# led_driver.net
KiCad netlist of a schematic drawn in Altium Designer
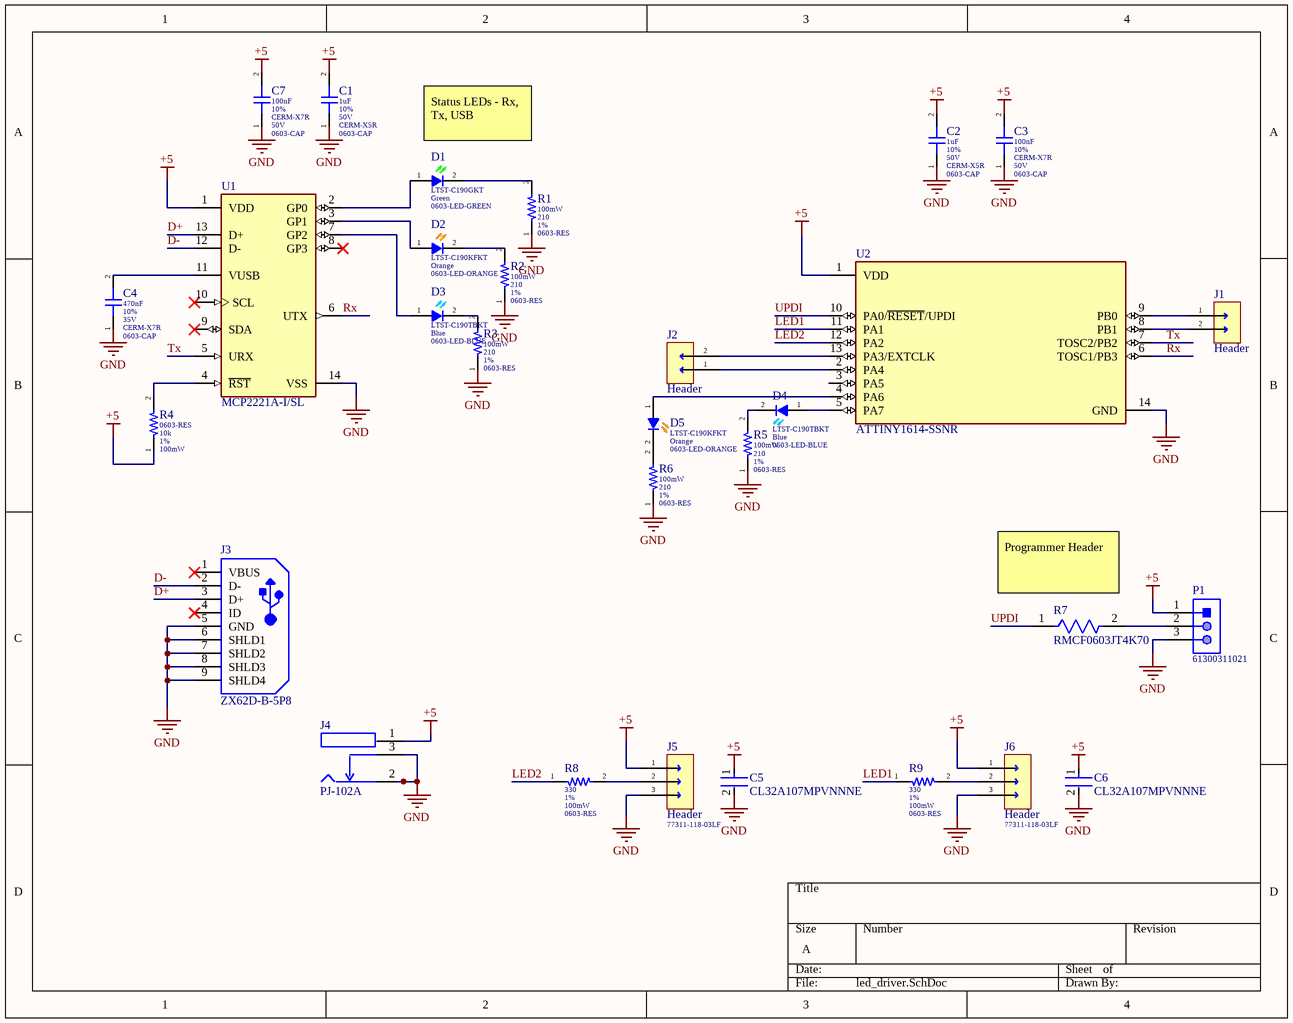
[diagram p0: led_driver.SchDoc]

(export (version "E")
  (design (tool "Eeschema 10.0.6"))
  (components
    (comp (ref "C1")
      (value "CAP SAMSUNG CL10A105KB8NNNC")
      (footprint "0603-CAP")
      (description "CAP CER 1UF 50V X5R 0603")
      (fields
        (field (name "MANUFACTURER") "Samsung")
        (field (name "MANUFACTURER PART NUMBER") "CL10A105KB8NNNC")
        (field (name "CAPACITANCE") "1uF")
        (field (name "TOLERANCE") "10%")
        (field (name "VOLTAGE RATING") "50V")
        (field (name "DIELECTRIC") "CERM-X5R")
      )
      (libsource (lib "MHYPE Devices") (part "CAP SAMSUNG CL10A105KB8NNNC"))
    )
    (comp (ref "C2")
      (value "CAP SAMSUNG CL10A105KB8NNNC")
      (footprint "0603-CAP")
      (description "CAP CER 1UF 50V X5R 0603")
      (fields
        (field (name "MANUFACTURER") "Samsung")
        (field (name "MANUFACTURER PART NUMBER") "CL10A105KB8NNNC")
        (field (name "CAPACITANCE") "1uF")
        (field (name "TOLERANCE") "10%")
        (field (name "VOLTAGE RATING") "50V")
        (field (name "DIELECTRIC") "CERM-X5R")
      )
      (libsource (lib "MHYPE Devices") (part "CAP SAMSUNG CL10A105KB8NNNC"))
    )
    (comp (ref "C3")
      (value "CAP TDK CGA3E2X7R1H104K080AA")
      (footprint "0603-CAP")
      (description "CAP CER 0.1UF 50V X7R 0603")
      (fields
        (field (name "MANUFACTURER") "TDK")
        (field (name "MANUFACTURER PART NUMBER") "CGA3E2X7R1H104K080AA")
        (field (name "CAPACITANCE") "100nF")
        (field (name "TOLERANCE") "10%")
        (field (name "DIELECTRIC") "CERM-X7R")
        (field (name "VOLTAGE") "50V")
      )
      (libsource (lib "MHYPE Devices") (part "CAP TDK CGA3E2X7R1H104K080AA"))
    )
    (comp (ref "C4")
      (value "CAP TDK CGA3E1X7R1V474K080AC")
      (footprint "0603-CAP")
      (description "CAP CER 0.47UF 35V X7R 0603")
      (fields
        (field (name "MANUFACTURER") "TDK")
        (field (name "MANUFACTURER PART NUMBER") "CGA3E1X7R1V474K080AC")
        (field (name "CAPACITANCE") "470nF")
        (field (name "TOLERANCE") "10%")
        (field (name "VOLTAGE RATING") "35V")
        (field (name "DIELECTRIC") "CERM-X7R")
      )
      (libsource (lib "MHYPE Devices") (part "CAP TDK CGA3E1X7R1V474K080AC"))
    )
    (comp (ref "C5")
      (value "CL32A107MPVNNNE")
      (footprint "FP-CL32-IPC_C")
      (description "Cap Ceramic 100uF 10V X5R ±20% SMD 1210 +85°C Embossed T/R")
      (fields (field (name "VOLTAGE") "10V") (field (name "TOLERANCE") "20%"))
      (libsource (lib "Altium Content Vault") (part "b4654b650e69147ec39a6b967a45e02"))
    )
    (comp (ref "C6")
      (value "CL32A107MPVNNNE")
      (footprint "FP-CL32-IPC_C")
      (description "Cap Ceramic 100uF 10V X5R ±20% SMD 1210 +85°C Embossed T/R")
      (fields (field (name "VOLTAGE") "10V") (field (name "TOLERANCE") "20%"))
      (libsource (lib "Altium Content Vault") (part "b4654b650e69147ec39a6b967a45e02"))
    )
    (comp (ref "C7")
      (value "CAP TDK CGA3E2X7R1H104K080AA")
      (footprint "0603-CAP")
      (description "CAP CER 0.1UF 50V X7R 0603")
      (fields
        (field (name "MANUFACTURER") "TDK")
        (field (name "MANUFACTURER PART NUMBER") "CGA3E2X7R1H104K080AA")
        (field (name "CAPACITANCE") "100nF")
        (field (name "TOLERANCE") "10%")
        (field (name "DIELECTRIC") "CERM-X7R")
        (field (name "VOLTAGE") "50V")
      )
      (libsource (lib "MHYPE Devices") (part "CAP TDK CGA3E2X7R1H104K080AA"))
    )
    (comp (ref "D1")
      (value "LED LITE-ON LTST-C190GKT")
      (footprint "0603-LED-GREEN")
      (description "LED GREEN CLEAR CHIP SMD")
      (fields
        (field (name "MANUFACTURER") "Vishay Lite-On")
        (field (name "VOLTAGE") "2V")
        (field (name "MANUFACTURER PART NUMBER") "LTST-C190GKT")
        (field (name "COLOR") "Green")
      )
      (libsource (lib "MHYPE Devices") (part "LED LITE-ON LTST-C190GKT"))
    )
    (comp (ref "D2")
      (value "LED LITE-ON LTST-C190KFKT")
      (footprint "0603-LED-ORANGE")
      (description "LED ORANGE CLEAR CHIP SMD")
      (fields
        (field (name "MANUFACTURER") "Vishay Lite-On")
        (field (name "MANUFACTURER PART NUMBER") "LTST-C190KFKT")
        (field (name "COLOR") "Orange")
      )
      (libsource (lib "MHYPE Devices") (part "LED LITE-ON LTST-C190KFKT"))
    )
    (comp (ref "D3")
      (value "LED LITE-ON LTST-C190TBKT")
      (footprint "0603-LED-BLUE")
      (description "LED BLUE CLEAR CHIP SMD")
      (fields
        (field (name "MANUFACTURER") "Vishay Lite-On")
        (field (name "MANUFACTURER PART NUMBER") "LTST-C190TBKT")
        (field (name "COLOR") "Blue")
      )
      (libsource (lib "MHYPE Devices") (part "LED LITE-ON LTST-C190TBKT"))
    )
    (comp (ref "D4")
      (value "LED LITE-ON LTST-C190TBKT")
      (footprint "0603-LED-BLUE")
      (description "LED BLUE CLEAR CHIP SMD")
      (fields
        (field (name "MANUFACTURER") "Vishay Lite-On")
        (field (name "MANUFACTURER PART NUMBER") "LTST-C190TBKT")
        (field (name "COLOR") "Blue")
      )
      (libsource (lib "MHYPE Devices") (part "LED LITE-ON LTST-C190TBKT"))
    )
    (comp (ref "D5")
      (value "LED LITE-ON LTST-C190KFKT")
      (footprint "0603-LED-ORANGE")
      (description "LED ORANGE CLEAR CHIP SMD")
      (fields
        (field (name "MANUFACTURER") "Vishay Lite-On")
        (field (name "MANUFACTURER PART NUMBER") "LTST-C190KFKT")
        (field (name "COLOR") "Orange")
      )
      (libsource (lib "MHYPE Devices") (part "LED LITE-ON LTST-C190KFKT"))
    )
    (comp (ref "J1")
      (value "Header")
      (footprint "HEADER 2POS 1ROW 2.54MM W/O BODY")
      (description "CONN HEADER VERT 2POS 2.54MM")
      (libsource (lib "") (part "HEADER 2POS_1"))
    )
    (comp (ref "J2")
      (value "Header")
      (footprint "HEADER 2POS 1ROW 2.54MM W/O BODY")
      (description "CONN HEADER VERT 2POS 2.54MM")
      (libsource (lib "MHYPE Connectors") (part "HEADER 2POS"))
    )
    (comp (ref "J3")
      (value "ZX62D-B-5P8")
      (footprint "HIRO-ZX62D-B-5P8_V")
      (fields (field (name "TOLERANCE") "10%"))
      (libsource (lib "Altium Content Vault") (part "USB-5-4SHLD"))
    )
    (comp (ref "J4")
      (value "PJ-102A")
      (footprint "FP-PJ-102A-MFG")
      (description "CONN PWR JACK 2X5.5MM SOLDER")
      (fields (field (name "MANUFACTURER") "CUI") (field (name "VOLTAGE") "24V"))
      (libsource (lib "Altium Content Vault") (part "0685d7ee7311ef3291d1b1b03391b7d"))
    )
    (comp (ref "J5")
      (value "Header")
      (footprint "HEADER 3POS 1ROW 2.54MM")
      (description "CONN HEADER VERT 3POS 2.54MM")
      (fields
        (field (name "MANUFACTURER") "Amphenol FCI")
        (field (name "MANUFACTURER PART NUMBER") "77311-118-03LF")
      )
      (libsource (lib "MHYPE Connectors") (part "HEADER AMPHENOL 77311-118-03LF"))
    )
    (comp (ref "J6")
      (value "Header")
      (footprint "HEADER 3POS 1ROW 2.54MM")
      (description "CONN HEADER VERT 3POS 2.54MM")
      (fields
        (field (name "MANUFACTURER") "Amphenol FCI")
        (field (name "MANUFACTURER PART NUMBER") "77311-118-03LF")
      )
      (libsource (lib "MHYPE Connectors") (part "HEADER AMPHENOL 77311-118-03LF"))
    )
    (comp (ref "P1")
      (value "61300311021")
      (footprint "61300311021")
      (description "THT Angled Pin Header WR-PHD, Pitch 2.54 mm, Single Row, 3 pins")
      (fields (field (name "MANUFACTURER") "Wurth Elektronik") (field (name "PUBLISHER") "WurthElektronik"))
      (libsource (lib "Altium Content Vault") (part "WE-CN-1P-M-R3"))
    )
    (comp (ref "R1")
      (value "RES KOA RK73H1JTTD2100F")
      (footprint "0603-RES")
      (description "RES 210 OHM 1% 1/8W 0603")
      (fields
        (field (name "MANUFACTURER") "KOA Speer")
        (field (name "MANUFACTURER PART NUMBER") "RK73H1JTTD2100F")
        (field (name "POWER RATING") "100mW")
        (field (name "RESISTANCE") "210")
        (field (name "TOLERANCE") "1%")
      )
      (libsource (lib "MHYPE Devices") (part "RES KOA RK73H1JTTD2100F"))
    )
    (comp (ref "R2")
      (value "RES KOA RK73H1JTTD2100F")
      (footprint "0603-RES")
      (description "RES 210 OHM 1% 1/8W 0603")
      (fields
        (field (name "MANUFACTURER") "KOA Speer")
        (field (name "MANUFACTURER PART NUMBER") "RK73H1JTTD2100F")
        (field (name "POWER RATING") "100mW")
        (field (name "RESISTANCE") "210")
        (field (name "TOLERANCE") "1%")
      )
      (libsource (lib "MHYPE Devices") (part "RES KOA RK73H1JTTD2100F"))
    )
    (comp (ref "R3")
      (value "RES KOA RK73H1JTTD2100F")
      (footprint "0603-RES")
      (description "RES 210 OHM 1% 1/8W 0603")
      (fields
        (field (name "MANUFACTURER") "KOA Speer")
        (field (name "MANUFACTURER PART NUMBER") "RK73H1JTTD2100F")
        (field (name "POWER RATING") "100mW")
        (field (name "RESISTANCE") "210")
        (field (name "TOLERANCE") "1%")
      )
      (libsource (lib "MHYPE Devices") (part "RES KOA RK73H1JTTD2100F"))
    )
    (comp (ref "R4")
      (value "RES BOURNS CR0603AFX-1002EAS")
      (footprint "0603-RES")
      (description "RESA-AS 0603 10K 1% 100MW TC100")
      (fields
        (field (name "MANUFACTURER") "Bourns")
        (field (name "MANUFACTURER PART NUMBER") "CR0603AFX-1002EAS")
        (field (name "RESISTANCE") "10k")
        (field (name "TOLERANCE") "1%")
        (field (name "POWER") "100mW")
      )
      (libsource (lib "MHYPE Devices") (part "RES BOURNS CR0603AFX-1002EAS"))
    )
    (comp (ref "R5")
      (value "RES KOA RK73H1JTTD2100F")
      (footprint "0603-RES")
      (description "RES 210 OHM 1% 1/8W 0603")
      (fields
        (field (name "MANUFACTURER") "KOA Speer")
        (field (name "MANUFACTURER PART NUMBER") "RK73H1JTTD2100F")
        (field (name "POWER RATING") "100mW")
        (field (name "RESISTANCE") "210")
        (field (name "TOLERANCE") "1%")
      )
      (libsource (lib "MHYPE Devices") (part "RES KOA RK73H1JTTD2100F"))
    )
    (comp (ref "R6")
      (value "RES KOA RK73H1JTTD2100F")
      (footprint "0603-RES")
      (description "RES 210 OHM 1% 1/8W 0603")
      (fields
        (field (name "MANUFACTURER") "KOA Speer")
        (field (name "MANUFACTURER PART NUMBER") "RK73H1JTTD2100F")
        (field (name "POWER RATING") "100mW")
        (field (name "RESISTANCE") "210")
        (field (name "TOLERANCE") "1%")
      )
      (libsource (lib "MHYPE Devices") (part "RES KOA RK73H1JTTD2100F"))
    )
    (comp (ref "R7")
      (value "RMCF0603JT4K70")
      (footprint "FP-RMCF0603-MFG")
      (description "RES 4.7K OHM 5% 1/10W 0603")
      (fields (field (name "TOLERANCE") "5%"))
      (libsource (lib "Altium Content Vault") (part "1029c3af85768c4190bb7ad29bc67b5"))
    )
    (comp (ref "R8")
      (value "RES KOA RK73H1JTTD3300F")
      (footprint "0603-RES")
      (description "RES 330 OHM 1% 1/8W 0603")
      (fields
        (field (name "MANUFACTURER") "KOA Speer")
        (field (name "MANUFACTURER PART NUMBER") "RK73H1JTTD3300F")
        (field (name "RESISTANCE") "330")
        (field (name "TOLERANCE") "1%")
        (field (name "POWER RATING") "100mW")
      )
      (libsource (lib "MHYPE Devices") (part "RES KOA RK73H1JTTD3300F"))
    )
    (comp (ref "R9")
      (value "RES KOA RK73H1JTTD3300F")
      (footprint "0603-RES")
      (description "RES 330 OHM 1% 1/8W 0603")
      (fields
        (field (name "MANUFACTURER") "KOA Speer")
        (field (name "MANUFACTURER PART NUMBER") "RK73H1JTTD3300F")
        (field (name "RESISTANCE") "330")
        (field (name "TOLERANCE") "1%")
        (field (name "POWER RATING") "100mW")
      )
      (libsource (lib "MHYPE Devices") (part "RES KOA RK73H1JTTD3300F"))
    )
    (comp (ref "U1")
      (value "MCP2221A-I/SL")
      (footprint "FP-C04-065-SL-MFG")
      (description "IC USB TO I2C/UART 14SOIC")
      (fields
        (field (name "OCTOPART") "https://octopart.com/mcp2221a-i%2Fsl-microchip-71704986")
        (field (name "MANUFACTURER") "Microchip")
      )
      (libsource (lib "Altium Content Vault") (part "1b53208594fde27bd45fc2fa1d78706"))
    )
    (comp (ref "U2")
      (value "ATTINY1614-SSNR")
      (footprint "FP-C04-065-D3X-MFG")
      (description "IC MCU 8BIT 16KB FLASH 14SOIC")
      (fields
        (field (name "OCTOPART") "https://octopart.com/attiny1614-ssnr-microchip-82955111")
        (field (name "MANUFACTURER") "Microchip")
      )
      (libsource (lib "Altium Content Vault") (part "5f3e37ca9bfbcbeb1dc30fd7d5509b7"))
    )
  )
  (nets
    (net (code "1") (name "+5") (class "Default")
      (node (ref "C1") (pin "2") (pinfunction "2_2") (pintype "passive"))
      (node (ref "C2") (pin "2") (pinfunction "2_2") (pintype "passive"))
      (node (ref "C3") (pin "2") (pinfunction "2_2") (pintype "passive"))
      (node (ref "C5") (pin "1") (pinfunction "1_1") (pintype "passive"))
      (node (ref "C6") (pin "1") (pinfunction "1_1") (pintype "passive"))
      (node (ref "C7") (pin "2") (pinfunction "2_2") (pintype "passive"))
      (node (ref "J4") (pin "1") (pinfunction "1_1") (pintype "passive"))
      (node (ref "J5") (pin "1") (pintype "passive"))
      (node (ref "J6") (pin "1") (pintype "passive"))
      (node (ref "P1") (pin "1") (pinfunction "1_1") (pintype "passive"))
      (node (ref "R4") (pin "1") (pinfunction "1_1") (pintype "passive"))
      (node (ref "U1") (pin "1") (pinfunction "VDD_1") (pintype "power_in"))
      (node (ref "U2") (pin "1") (pinfunction "VDD_1") (pintype "power_in"))
    )
    (net (code "2") (name "/D+") (class "Default")
      (node (ref "J3") (pin "3") (pinfunction "D+_3") (pintype "passive"))
      (node (ref "U1") (pin "13") (pinfunction "D+_13") (pintype "power_in"))
    )
    (net (code "3") (name "/D-") (class "Default")
      (node (ref "J3") (pin "2") (pinfunction "D-_2") (pintype "passive"))
      (node (ref "U1") (pin "12") (pinfunction "D-_12") (pintype "power_in"))
    )
    (net (code "4") (name "/LED1") (class "Default")
      (node (ref "R9") (pin "1") (pinfunction "1_1") (pintype "passive"))
      (node (ref "U2") (pin "11") (pinfunction "PA1_11") (pintype "bidirectional"))
    )
    (net (code "5") (name "/LED2") (class "Default")
      (node (ref "R8") (pin "1") (pinfunction "1_1") (pintype "passive"))
      (node (ref "U2") (pin "12") (pinfunction "PA2_12") (pintype "bidirectional"))
    )
    (net (code "6") (name "/Rx") (class "Default")
      (node (ref "U1") (pin "6") (pinfunction "UTX_6") (pintype "output"))
      (node (ref "U2") (pin "6") (pinfunction "TOSC1/PB3_6") (pintype "bidirectional"))
    )
    (net (code "7") (name "/Tx") (class "Default")
      (node (ref "U1") (pin "5") (pinfunction "URX_5") (pintype "input"))
      (node (ref "U2") (pin "7") (pinfunction "TOSC2/PB2_7") (pintype "bidirectional"))
    )
    (net (code "8") (name "/UPDI") (class "Default")
      (node (ref "R7") (pin "1") (pinfunction "1_1") (pintype "passive"))
      (node (ref "U2") (pin "10") (pinfunction "PA0/~{RESET}/UPDI_10") (pintype "bidirectional"))
    )
    (net (code "9") (name "GND") (class "Default")
      (node (ref "C1") (pin "1") (pinfunction "1_1") (pintype "passive"))
      (node (ref "C2") (pin "1") (pinfunction "1_1") (pintype "passive"))
      (node (ref "C3") (pin "1") (pinfunction "1_1") (pintype "passive"))
      (node (ref "C4") (pin "1") (pinfunction "1_1") (pintype "passive"))
      (node (ref "C5") (pin "2") (pinfunction "2_2") (pintype "passive"))
      (node (ref "C6") (pin "2") (pinfunction "2_2") (pintype "passive"))
      (node (ref "C7") (pin "1") (pinfunction "1_1") (pintype "passive"))
      (node (ref "J3") (pin "5") (pinfunction "GND_5") (pintype "passive"))
      (node (ref "J3") (pin "6") (pinfunction "SHLD1_6") (pintype "passive"))
      (node (ref "J3") (pin "7") (pinfunction "SHLD2_7") (pintype "passive"))
      (node (ref "J3") (pin "8") (pinfunction "SHLD3_8") (pintype "passive"))
      (node (ref "J3") (pin "9") (pinfunction "SHLD4_9") (pintype "passive"))
      (node (ref "J4") (pin "2") (pinfunction "2_2") (pintype "passive"))
      (node (ref "J4") (pin "3") (pinfunction "3_3") (pintype "passive"))
      (node (ref "J5") (pin "3") (pintype "passive"))
      (node (ref "J6") (pin "3") (pintype "passive"))
      (node (ref "P1") (pin "3") (pinfunction "3_3") (pintype "passive"))
      (node (ref "R1") (pin "1") (pinfunction "1_1") (pintype "passive"))
      (node (ref "R2") (pin "1") (pinfunction "1_1") (pintype "passive"))
      (node (ref "R3") (pin "1") (pinfunction "1_1") (pintype "passive"))
      (node (ref "R5") (pin "1") (pinfunction "1_1") (pintype "passive"))
      (node (ref "R6") (pin "1") (pinfunction "1_1") (pintype "passive"))
      (node (ref "U1") (pin "14") (pinfunction "VSS_14") (pintype "power_in"))
      (node (ref "U2") (pin "14") (pinfunction "GND_14") (pintype "power_in"))
    )
    (net (code "10") (name "Net-(D1-Pad2)") (class "Default")
      (node (ref "D1") (pin "2") (pinfunction "2_2") (pintype "passive"))
      (node (ref "R1") (pin "2") (pinfunction "2_2") (pintype "passive"))
    )
    (net (code "11") (name "Net-(D2-Pad2)") (class "Default")
      (node (ref "D2") (pin "2") (pinfunction "2_2") (pintype "passive"))
      (node (ref "R2") (pin "2") (pinfunction "2_2") (pintype "passive"))
    )
    (net (code "12") (name "Net-(D3-Pad2)") (class "Default")
      (node (ref "D3") (pin "2") (pinfunction "2_2") (pintype "passive"))
      (node (ref "R3") (pin "2") (pinfunction "2_2") (pintype "passive"))
    )
    (net (code "13") (name "Net-(D4-Pad2)") (class "Default")
      (node (ref "D4") (pin "2") (pinfunction "2_2") (pintype "passive"))
      (node (ref "R5") (pin "2") (pinfunction "2_2") (pintype "passive"))
    )
    (net (code "14") (name "Net-(D5-Pad2)") (class "Default")
      (node (ref "D5") (pin "2") (pinfunction "2_2") (pintype "passive"))
      (node (ref "R6") (pin "2") (pinfunction "2_2") (pintype "passive"))
    )
    (net (code "15") (name "Net-(J5-Pad2)") (class "Default")
      (node (ref "J5") (pin "2") (pintype "passive"))
      (node (ref "R8") (pin "2") (pinfunction "2_2") (pintype "passive"))
    )
    (net (code "16") (name "Net-(J6-Pad2)") (class "Default")
      (node (ref "J6") (pin "2") (pintype "passive"))
      (node (ref "R9") (pin "2") (pinfunction "2_2") (pintype "passive"))
    )
    (net (code "17") (name "Net-(P1-Pad2)") (class "Default")
      (node (ref "P1") (pin "2") (pinfunction "2_2") (pintype "passive"))
      (node (ref "R7") (pin "2") (pinfunction "2_2") (pintype "passive"))
    )
    (net (code "18") (name "Net-(U1-GP0)") (class "Default")
      (node (ref "D1") (pin "1") (pinfunction "1_1") (pintype "passive"))
      (node (ref "U1") (pin "2") (pinfunction "GP0_2") (pintype "bidirectional"))
    )
    (net (code "19") (name "Net-(U1-GP1)") (class "Default")
      (node (ref "D2") (pin "1") (pinfunction "1_1") (pintype "passive"))
      (node (ref "U1") (pin "3") (pinfunction "GP1_3") (pintype "bidirectional"))
    )
    (net (code "20") (name "Net-(U1-GP2)") (class "Default")
      (node (ref "D3") (pin "1") (pinfunction "1_1") (pintype "passive"))
      (node (ref "U1") (pin "7") (pinfunction "GP2_7") (pintype "bidirectional"))
    )
    (net (code "21") (name "Net-(U1-VUSB)") (class "Default")
      (node (ref "C4") (pin "2") (pinfunction "2_2") (pintype "passive"))
      (node (ref "U1") (pin "11") (pinfunction "VUSB_11") (pintype "power_in"))
    )
    (net (code "22") (name "Net-(U1-~{RST})") (class "Default")
      (node (ref "R4") (pin "2") (pinfunction "2_2") (pintype "passive"))
      (node (ref "U1") (pin "4") (pinfunction "~{RST}_4") (pintype "input"))
    )
    (net (code "23") (name "Net-(U2-PA3{slash}EXTCLK)") (class "Default")
      (node (ref "J2") (pin "2") (pintype "passive"))
      (node (ref "U2") (pin "13") (pinfunction "PA3/EXTCLK_13") (pintype "bidirectional"))
    )
    (net (code "24") (name "Net-(U2-PA4)") (class "Default")
      (node (ref "J2") (pin "1") (pintype "passive"))
      (node (ref "U2") (pin "2") (pinfunction "PA4_2") (pintype "bidirectional"))
    )
    (net (code "25") (name "Net-(U2-PA6)") (class "Default")
      (node (ref "D5") (pin "1") (pinfunction "1_1") (pintype "passive"))
      (node (ref "U2") (pin "4") (pinfunction "PA6_4") (pintype "bidirectional"))
    )
    (net (code "26") (name "Net-(U2-PA7)") (class "Default")
      (node (ref "D4") (pin "1") (pinfunction "1_1") (pintype "passive"))
      (node (ref "U2") (pin "5") (pinfunction "PA7_5") (pintype "bidirectional"))
    )
    (net (code "27") (name "Net-(U2-PB0)") (class "Default")
      (node (ref "J1") (pin "1") (pintype "passive"))
      (node (ref "U2") (pin "9") (pinfunction "PB0_9") (pintype "bidirectional"))
    )
    (net (code "28") (name "Net-(U2-PB1)") (class "Default")
      (node (ref "J1") (pin "2") (pintype "passive"))
      (node (ref "U2") (pin "8") (pinfunction "PB1_8") (pintype "bidirectional"))
    )
    (net (code "29") (name "unconnected-(J3-ID-Pad4)") (class "Default")
      (node (ref "J3") (pin "4") (pinfunction "ID_4") (pintype "passive+no_connect"))
    )
    (net (code "30") (name "unconnected-(J3-VBUS-Pad1)") (class "Default")
      (node (ref "J3") (pin "1") (pinfunction "VBUS_1") (pintype "passive+no_connect"))
    )
    (net (code "31") (name "unconnected-(U1-GP3-Pad8)") (class "Default")
      (node (ref "U1") (pin "8") (pinfunction "GP3_8") (pintype "bidirectional+no_connect"))
    )
    (net (code "32") (name "unconnected-(U1-SCL-Pad10)") (class "Default")
      (node (ref "U1") (pin "10") (pinfunction "SCL_10") (pintype "input+no_connect"))
    )
    (net (code "33") (name "unconnected-(U1-SDA-Pad9)") (class "Default")
      (node (ref "U1") (pin "9") (pinfunction "SDA_9") (pintype "bidirectional+no_connect"))
    )
    (net (code "34") (name "unconnected-(U2-PA5-Pad3)") (class "Default")
      (node (ref "U2") (pin "3") (pinfunction "PA5_3") (pintype "bidirectional"))
    )
  )
)
